# CAN_bus.net
KiCad netlist of a schematic drawn in Altium Designer
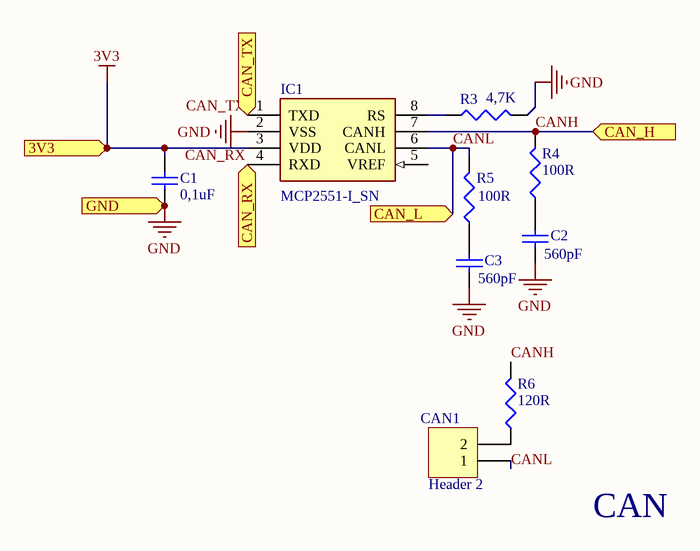
[diagram p0: CAN bus.SchDoc]

(export (version "E")
  (design (tool "Eeschema 10.0.6"))
  (components
    (comp (ref "C1")
      (value "0,1uF")
      (footprint "1608[0603]")
      (description "Capacitor (Semiconductor SIM Model)")
      (fields (field (name "PUBLISHER") "Altium Limited"))
      (libsource (lib "Miscellaneous Devices") (part "Cap Semi"))
    )
    (comp (ref "C2")
      (value "560pF")
      (footprint "1608[0603]")
      (description "Capacitor (Semiconductor SIM Model)")
      (fields (field (name "PUBLISHER") "Altium Limited"))
      (libsource (lib "Miscellaneous Devices") (part "Cap Semi"))
    )
    (comp (ref "C3")
      (value "560pF")
      (footprint "1608[0603]")
      (description "Capacitor (Semiconductor SIM Model)")
      (fields (field (name "PUBLISHER") "Altium Limited"))
      (libsource (lib "Miscellaneous Devices") (part "Cap Semi"))
    )
    (comp (ref "CAN1")
      (value "Header 2")
      (footprint "HDR1X2")
      (description "Header, 2-Pin")
      (fields (field (name "PUBLISHER") "Altium Limited"))
      (libsource (lib "Miscellaneous Connectors") (part "Header 2"))
    )
    (comp (ref "IC1")
      (value "MCP2551-I_SN")
      (footprint "SOIC127P600X175-8N")
      (description "Integrated Circuit")
      (fields
        (field (name "MANUFACTURER_PART_NUMBER") "MCP2551-I/SN")
        (field (name "MOUSER PART NUMBER") "579-MCP2551-I/SN")
      )
      (libsource (lib "*") (part "MCP2551-I_SN"))
    )
    (comp (ref "R3")
      (value "4,7K")
      (footprint "J1-0603")
      (description "Resistor")
      (fields (field (name "PUBLISHER") "Altium Limited"))
      (libsource (lib "Miscellaneous Devices") (part "Res3"))
    )
    (comp (ref "R4")
      (value "100R")
      (footprint "J1-0603")
      (description "Resistor")
      (fields (field (name "PUBLISHER") "Altium Limited"))
      (libsource (lib "Miscellaneous Devices") (part "Res3"))
    )
    (comp (ref "R5")
      (value "100R")
      (footprint "J1-0603")
      (description "Resistor")
      (fields (field (name "PUBLISHER") "Altium Limited"))
      (libsource (lib "Miscellaneous Devices") (part "Res3"))
    )
    (comp (ref "R6")
      (value "120R")
      (footprint "J1-0603")
      (description "Resistor")
      (fields (field (name "PUBLISHER") "Altium Limited"))
      (libsource (lib "Miscellaneous Devices") (part "Res3"))
    )
  )
  (nets
    (net (code "1") (name "/CANH") (class "Default")
      (node (ref "IC1") (pin "7") (pinfunction "CANH_7") (pintype "passive"))
      (node (ref "R4") (pin "2") (pinfunction "2_2") (pintype "passive"))
      (node (ref "R6") (pin "2") (pinfunction "2_2") (pintype "passive"))
    )
    (net (code "2") (name "/CANL") (class "Default")
      (node (ref "CAN1") (pin "1") (pinfunction "1_1") (pintype "passive"))
      (node (ref "IC1") (pin "6") (pinfunction "CANL_6") (pintype "passive"))
      (node (ref "R5") (pin "2") (pinfunction "2_2") (pintype "passive"))
    )
    (net (code "3") (name "/CAN_RX") (class "Default")
      (node (ref "IC1") (pin "4") (pinfunction "RXD_4") (pintype "passive"))
    )
    (net (code "4") (name "/CAN_TX") (class "Default")
      (node (ref "IC1") (pin "1") (pinfunction "TXD_1") (pintype "passive"))
    )
    (net (code "5") (name "3V3") (class "Default")
      (node (ref "C1") (pin "1") (pinfunction "1_1") (pintype "passive"))
      (node (ref "IC1") (pin "3") (pinfunction "VDD_3") (pintype "power_in"))
    )
    (net (code "6") (name "GND") (class "Default")
      (node (ref "C1") (pin "2") (pinfunction "2_2") (pintype "passive"))
      (node (ref "C2") (pin "2") (pinfunction "2_2") (pintype "passive"))
      (node (ref "C3") (pin "2") (pinfunction "2_2") (pintype "passive"))
      (node (ref "IC1") (pin "2") (pinfunction "VSS_2") (pintype "power_in"))
      (node (ref "R3") (pin "2") (pinfunction "2_2") (pintype "passive"))
    )
    (net (code "7") (name "Net-(C2-Pad1)") (class "Default")
      (node (ref "C2") (pin "1") (pinfunction "1_1") (pintype "passive"))
      (node (ref "R4") (pin "1") (pinfunction "1_1") (pintype "passive"))
    )
    (net (code "8") (name "Net-(C3-Pad1)") (class "Default")
      (node (ref "C3") (pin "1") (pinfunction "1_1") (pintype "passive"))
      (node (ref "R5") (pin "1") (pinfunction "1_1") (pintype "passive"))
    )
    (net (code "9") (name "Net-(CAN1-Pad2)") (class "Default")
      (node (ref "CAN1") (pin "2") (pinfunction "2_2") (pintype "passive"))
      (node (ref "R6") (pin "1") (pinfunction "1_1") (pintype "passive"))
    )
    (net (code "10") (name "Net-(IC1-RS)") (class "Default")
      (node (ref "IC1") (pin "8") (pinfunction "RS_8") (pintype "passive"))
      (node (ref "R3") (pin "1") (pinfunction "1_1") (pintype "passive"))
    )
    (net (code "11") (name "unconnected-(IC1-VREF-Pad5)") (class "Default")
      (node (ref "IC1") (pin "5") (pinfunction "VREF_5") (pintype "input"))
    )
  )
)
